# MEFI.net
KiCad netlist of a schematic drawn in EAGLE
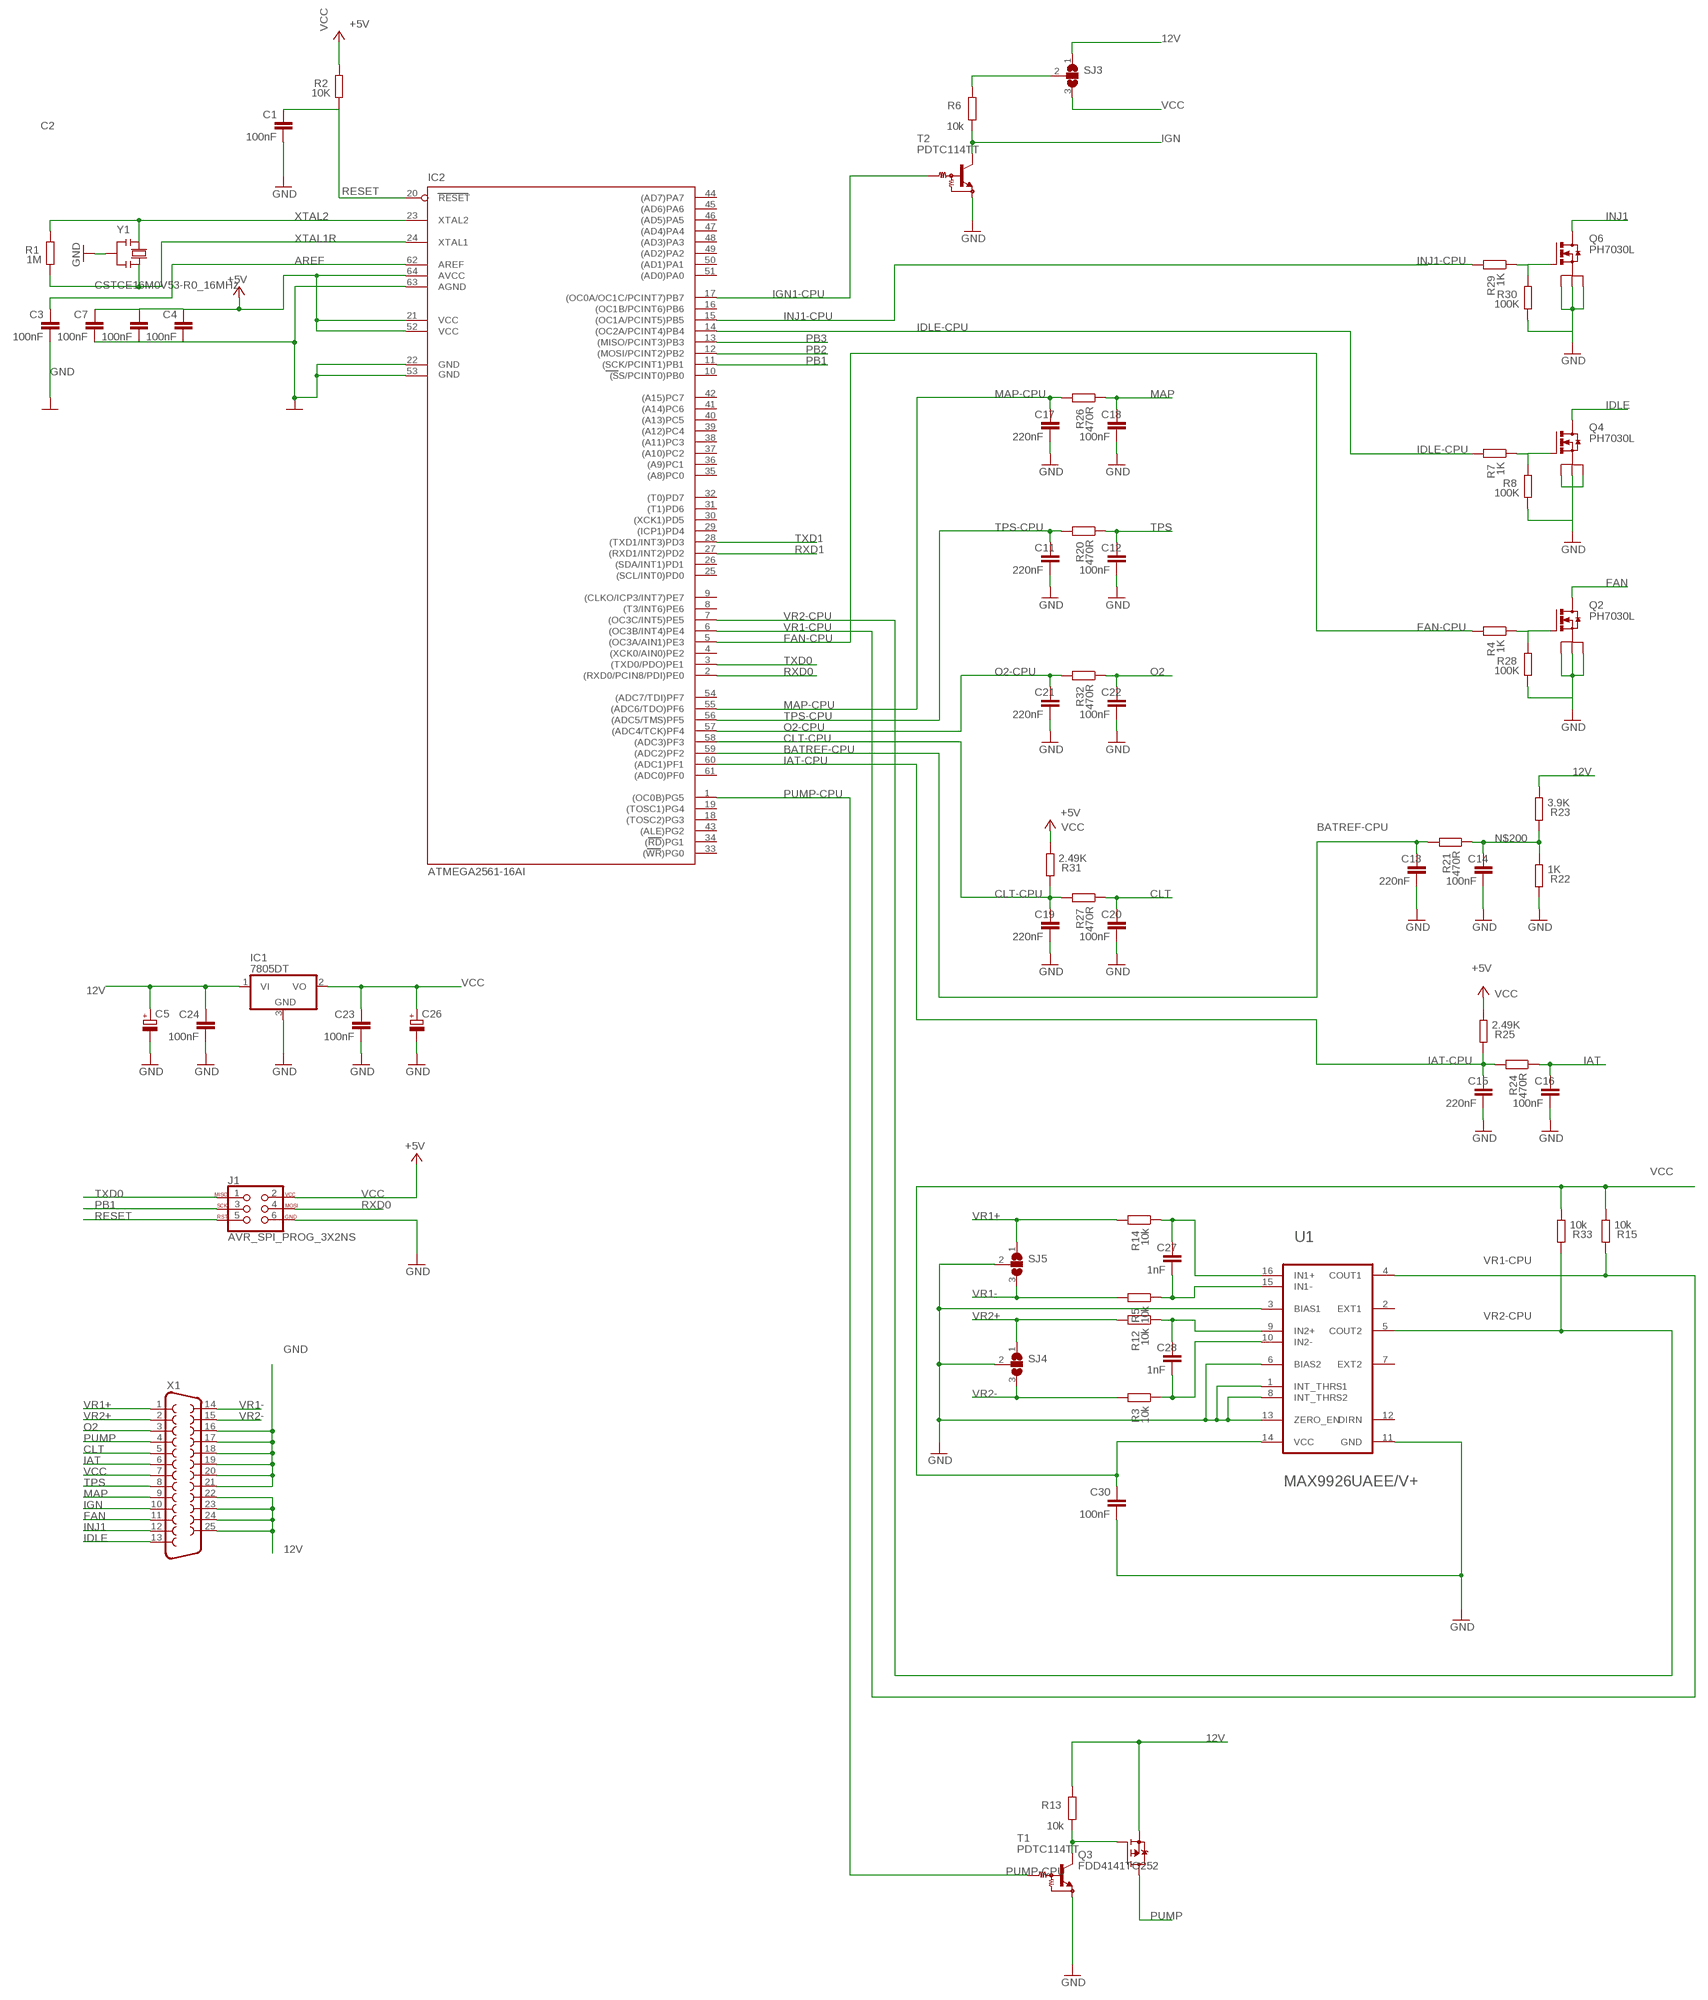
[diagram p0: schematic, sheet 1]

(export (version "E")
  (design (tool "Eeschema 10.0.6"))
  (components
    (comp (ref "C1")
      (value "100nF")
      (footprint "eagle-import:C0805")
      (libsource (lib "eagle-import") (part "C-EUC0805"))
    )
    (comp (ref "C2")
      (value "100nF")
      (footprint "eagle-import:C0805")
      (libsource (lib "eagle-import") (part "C-EUC0805"))
    )
    (comp (ref "C3")
      (value "100nF")
      (footprint "eagle-import:C0805")
      (libsource (lib "eagle-import") (part "C-EUC0805"))
    )
    (comp (ref "C4")
      (value "100nF")
      (footprint "eagle-import:C0805")
      (libsource (lib "eagle-import") (part "C-EUC0805"))
    )
    (comp (ref "C5")
      (value "CPOL-EUTT2D7L")
      (footprint "eagle-import:TT2D7L")
      (libsource (lib "eagle-import") (part "CPOL-EUTT2D7L"))
    )
    (comp (ref "C7")
      (value "100nF")
      (footprint "eagle-import:C0805")
      (libsource (lib "eagle-import") (part "C-EUC0805"))
    )
    (comp (ref "C11")
      (value "220nF")
      (footprint "eagle-import:C0805")
      (libsource (lib "eagle-import") (part "C-EUC0805"))
    )
    (comp (ref "C12")
      (value "100nF")
      (footprint "eagle-import:C0805")
      (libsource (lib "eagle-import") (part "C-EUC0805"))
    )
    (comp (ref "C13")
      (value "220nF")
      (footprint "eagle-import:C0805")
      (libsource (lib "eagle-import") (part "C-EUC0805"))
    )
    (comp (ref "C14")
      (value "100nF")
      (footprint "eagle-import:C0805")
      (libsource (lib "eagle-import") (part "C-EUC0805"))
    )
    (comp (ref "C15")
      (value "220nF")
      (footprint "eagle-import:C0805")
      (libsource (lib "eagle-import") (part "C-EUC0805"))
    )
    (comp (ref "C16")
      (value "100nF")
      (footprint "eagle-import:C0805")
      (libsource (lib "eagle-import") (part "C-EUC0805"))
    )
    (comp (ref "C17")
      (value "220nF")
      (footprint "eagle-import:C0805")
      (fields (field (name "SPICEPREFIX") "C"))
      (libsource (lib "eagle-import") (part "C-EUC0805"))
    )
    (comp (ref "C18")
      (value "100nF")
      (footprint "eagle-import:C0805")
      (libsource (lib "eagle-import") (part "C-EUC0805"))
    )
    (comp (ref "C19")
      (value "220nF")
      (footprint "eagle-import:C0805")
      (libsource (lib "eagle-import") (part "C-EUC0805"))
    )
    (comp (ref "C20")
      (value "100nF")
      (footprint "eagle-import:C0805")
      (libsource (lib "eagle-import") (part "C-EUC0805"))
    )
    (comp (ref "C21")
      (value "220nF")
      (footprint "eagle-import:C0805")
      (libsource (lib "eagle-import") (part "C-EUC0805"))
    )
    (comp (ref "C22")
      (value "100nF")
      (footprint "eagle-import:C0805")
      (libsource (lib "eagle-import") (part "C-EUC0805"))
    )
    (comp (ref "C23")
      (value "100nF")
      (footprint "eagle-import:C0805")
      (libsource (lib "eagle-import") (part "C-EUC0805"))
    )
    (comp (ref "C24")
      (value "100nF")
      (footprint "eagle-import:C0805")
      (libsource (lib "eagle-import") (part "C-EUC0805"))
    )
    (comp (ref "C26")
      (value "CPOL-EUTT2D7L")
      (footprint "eagle-import:TT2D7L")
      (libsource (lib "eagle-import") (part "CPOL-EUTT2D7L"))
    )
    (comp (ref "C27")
      (value "1nF")
      (footprint "eagle-import:C0805")
      (libsource (lib "eagle-import") (part "C-EUC0805"))
    )
    (comp (ref "C28")
      (value "1nF")
      (footprint "eagle-import:C0805")
      (libsource (lib "eagle-import") (part "C-EUC0805"))
    )
    (comp (ref "C30")
      (value "100nF")
      (footprint "eagle-import:C0805")
      (libsource (lib "eagle-import") (part "C-EUC0805"))
    )
    (comp (ref "IC1")
      (value "7805DT")
      (footprint "eagle-import:TO252")
      (libsource (lib "eagle-import") (part "78DT05"))
    )
    (comp (ref "IC2")
      (value "ATMEGA2561-16AI")
      (footprint "eagle-import:TQFP64")
      (libsource (lib "eagle-import") (part "ATMEGA2561AI-16"))
    )
    (comp (ref "J1")
      (value "AVR_SPI_PROG_3X2NS")
      (footprint "eagle-import:2X3-NS")
      (fields (field (name "SPICEPREFIX") "X"))
      (libsource (lib "eagle-import") (part "AVR_SPI_PROG_3X2NS"))
    )
    (comp (ref "Q2")
      (value "PH7030L")
      (footprint "eagle-import:SOT669")
      (libsource (lib "eagle-import") (part "PH7030L"))
    )
    (comp (ref "Q3")
      (value "FDD4141TO252")
      (footprint "eagle-import:TO252")
      (libsource (lib "eagle-import") (part "FDD4141TO252"))
    )
    (comp (ref "Q4")
      (value "PH7030L")
      (footprint "eagle-import:SOT669")
      (libsource (lib "eagle-import") (part "PH7030L"))
    )
    (comp (ref "Q6")
      (value "PH7030L")
      (footprint "eagle-import:SOT669")
      (libsource (lib "eagle-import") (part "PH7030L"))
    )
    (comp (ref "R1")
      (value "1M")
      (footprint "eagle-import:R0805")
      (libsource (lib "eagle-import") (part "R-EU_R0805"))
    )
    (comp (ref "R2")
      (value "10K")
      (footprint "eagle-import:R0805")
      (libsource (lib "eagle-import") (part "R-EU_R0805"))
    )
    (comp (ref "R3")
      (value "10k")
      (footprint "eagle-import:R0805")
      (libsource (lib "eagle-import") (part "R-EU_R0805"))
    )
    (comp (ref "R4")
      (value "1K")
      (footprint "eagle-import:R0805")
      (libsource (lib "eagle-import") (part "R-EU_R0805"))
    )
    (comp (ref "R5")
      (value "10k")
      (footprint "eagle-import:R0805")
      (libsource (lib "eagle-import") (part "R-EU_R0805"))
    )
    (comp (ref "R6")
      (value "10k")
      (footprint "eagle-import:R0805")
      (libsource (lib "eagle-import") (part "R-EU_R0805"))
    )
    (comp (ref "R7")
      (value "1K")
      (footprint "eagle-import:R0805")
      (libsource (lib "eagle-import") (part "R-EU_R0805"))
    )
    (comp (ref "R8")
      (value "100K")
      (footprint "eagle-import:R0805")
      (libsource (lib "eagle-import") (part "R-EU_R0805"))
    )
    (comp (ref "R12")
      (value "10k")
      (footprint "eagle-import:R0805")
      (libsource (lib "eagle-import") (part "R-EU_R0805"))
    )
    (comp (ref "R13")
      (value "10k")
      (footprint "eagle-import:R0805")
      (libsource (lib "eagle-import") (part "R-EU_R0805"))
    )
    (comp (ref "R14")
      (value "10k")
      (footprint "eagle-import:R0805")
      (libsource (lib "eagle-import") (part "R-EU_R0805"))
    )
    (comp (ref "R15")
      (value "10k")
      (footprint "eagle-import:R0805")
      (libsource (lib "eagle-import") (part "R-EU_R0805"))
    )
    (comp (ref "R20")
      (value "470R")
      (footprint "eagle-import:R0805")
      (libsource (lib "eagle-import") (part "R-EU_R0805"))
    )
    (comp (ref "R21")
      (value "470R")
      (footprint "eagle-import:R0805")
      (libsource (lib "eagle-import") (part "R-EU_R0805"))
    )
    (comp (ref "R22")
      (value "1K")
      (footprint "eagle-import:R0805")
      (libsource (lib "eagle-import") (part "R-EU_R0805"))
    )
    (comp (ref "R23")
      (value "3.9K")
      (footprint "eagle-import:R0805")
      (libsource (lib "eagle-import") (part "R-EU_R0805"))
    )
    (comp (ref "R24")
      (value "470R")
      (footprint "eagle-import:R0805")
      (libsource (lib "eagle-import") (part "R-EU_R0805"))
    )
    (comp (ref "R25")
      (value "2.49K")
      (footprint "eagle-import:R0805")
      (libsource (lib "eagle-import") (part "R-EU_R0805"))
    )
    (comp (ref "R26")
      (value "470R")
      (footprint "eagle-import:R0805")
      (libsource (lib "eagle-import") (part "R-EU_R0805"))
    )
    (comp (ref "R27")
      (value "470R")
      (footprint "eagle-import:R0805")
      (libsource (lib "eagle-import") (part "R-EU_R0805"))
    )
    (comp (ref "R28")
      (value "100K")
      (footprint "eagle-import:R0805")
      (libsource (lib "eagle-import") (part "R-EU_R0805"))
    )
    (comp (ref "R29")
      (value "1K")
      (footprint "eagle-import:R0805")
      (libsource (lib "eagle-import") (part "R-EU_R0805"))
    )
    (comp (ref "R30")
      (value "100K")
      (footprint "eagle-import:R0805")
      (libsource (lib "eagle-import") (part "R-EU_R0805"))
    )
    (comp (ref "R31")
      (value "2.49K")
      (footprint "eagle-import:R0805")
      (libsource (lib "eagle-import") (part "R-EU_R0805"))
    )
    (comp (ref "R32")
      (value "470R")
      (footprint "eagle-import:R0805")
      (libsource (lib "eagle-import") (part "R-EU_R0805"))
    )
    (comp (ref "R33")
      (value "10k")
      (footprint "eagle-import:R0805")
      (libsource (lib "eagle-import") (part "R-EU_R0805"))
    )
    (comp (ref "SJ3")
      (value "SJ2W")
      (footprint "eagle-import:SJ_2")
      (libsource (lib "eagle-import") (part "SJ2W"))
    )
    (comp (ref "SJ4")
      (value "SJ2W")
      (footprint "eagle-import:SJ_2")
      (libsource (lib "eagle-import") (part "SJ2W"))
    )
    (comp (ref "SJ5")
      (value "SJ2W")
      (footprint "eagle-import:SJ_2")
      (libsource (lib "eagle-import") (part "SJ2W"))
    )
    (comp (ref "T1")
      (value "PDTC114TT")
      (footprint "eagle-import:SC59-BEC")
      (libsource (lib "eagle-import") (part "-NPN_DRIVER-SC59-BECMUN2214T1"))
    )
    (comp (ref "T2")
      (value "PDTC114TT")
      (footprint "eagle-import:SC59-BEC")
      (libsource (lib "eagle-import") (part "-NPN_DRIVER-SC59-BECMUN2214T1"))
    )
    (comp (ref "U1")
      (value "MAXIM_MAX9926UAEE-V+MAXIM_MAX9926UAEE-V+_0_0")
      (footprint "eagle-import:MAXIM_MAX9926UAEE-V+_0")
      (fields (field (name "MF") "Maxim") (field (name "MPN") "MAX9926UAEE/V+"))
      (libsource (lib "eagle-import") (part "MAXIM_MAX9926UAEE-V+MAXIM_MAX9926UAEE-V+_0_0"))
    )
    (comp (ref "X1")
      (value "F25D")
      (footprint "eagle-import:F25D")
      (libsource (lib "eagle-import") (part "F25D"))
    )
    (comp (ref "Y1")
      (value "CSTCE16M0V53-R0_16MHz")
      (footprint "eagle-import:RESONATOR")
      (libsource (lib "eagle-import") (part "RESONATORMU"))
    )
  )
  (nets
    (net (code "1") (name "+5V") (class "Default")
      (node (ref "C2") (pin "1") (pinfunction "1_1") (pintype "passive"))
      (node (ref "C23") (pin "1") (pinfunction "1_1") (pintype "passive"))
      (node (ref "C26") (pin "+") (pinfunction "+_+") (pintype "passive"))
      (node (ref "C30") (pin "1") (pinfunction "1_1") (pintype "passive"))
      (node (ref "C4") (pin "1") (pinfunction "1_1") (pintype "passive"))
      (node (ref "C7") (pin "1") (pinfunction "1_1") (pintype "passive"))
      (node (ref "IC1") (pin "2") (pinfunction "VO_2") (pintype "passive"))
      (node (ref "IC2") (pin "21") (pinfunction "VCC_21") (pintype "power_in"))
      (node (ref "IC2") (pin "52") (pinfunction "VCC1_52") (pintype "power_in"))
      (node (ref "IC2") (pin "64") (pinfunction "AVCC_64") (pintype "power_in"))
      (node (ref "J1") (pin "2") (pinfunction "2_2") (pintype "passive"))
      (node (ref "R15") (pin "1") (pinfunction "1_1") (pintype "passive"))
      (node (ref "R2") (pin "2") (pinfunction "2_2") (pintype "passive"))
      (node (ref "R25") (pin "1") (pinfunction "1_1") (pintype "passive"))
      (node (ref "R31") (pin "1") (pinfunction "1_1") (pintype "passive"))
      (node (ref "R33") (pin "1") (pinfunction "1_1") (pintype "passive"))
      (node (ref "SJ3") (pin "3") (pinfunction "3_3") (pintype "passive"))
      (node (ref "U1") (pin "14") (pinfunction "VCC_14") (pintype "power_in"))
      (node (ref "X1") (pin "7") (pinfunction "7_7") (pintype "passive"))
    )
    (net (code "2") (name "/12V") (class "Default")
      (node (ref "C24") (pin "1") (pinfunction "1_1") (pintype "passive"))
      (node (ref "C5") (pin "+") (pinfunction "+_+") (pintype "passive"))
      (node (ref "IC1") (pin "1") (pinfunction "VI_1") (pintype "input"))
      (node (ref "Q3") (pin "2") (pinfunction "S_2") (pintype "passive"))
      (node (ref "R13") (pin "2") (pinfunction "2_2") (pintype "passive"))
      (node (ref "R23") (pin "1") (pinfunction "1_1") (pintype "passive"))
      (node (ref "SJ3") (pin "1") (pinfunction "1_1") (pintype "passive"))
      (node (ref "X1") (pin "22") (pinfunction "22_22") (pintype "passive"))
      (node (ref "X1") (pin "23") (pinfunction "23_23") (pintype "passive"))
      (node (ref "X1") (pin "24") (pinfunction "24_24") (pintype "passive"))
      (node (ref "X1") (pin "25") (pinfunction "25_25") (pintype "passive"))
    )
    (net (code "3") (name "/AREF") (class "Default")
      (node (ref "C3") (pin "1") (pinfunction "1_1") (pintype "passive"))
      (node (ref "IC2") (pin "62") (pinfunction "AREF_62") (pintype "bidirectional"))
    )
    (net (code "4") (name "/BATREF-CPU") (class "Default")
      (node (ref "C13") (pin "1") (pinfunction "1_1") (pintype "passive"))
      (node (ref "IC2") (pin "59") (pinfunction "(ADC2)PF2_59") (pintype "bidirectional"))
      (node (ref "R21") (pin "2") (pinfunction "2_2") (pintype "passive"))
    )
    (net (code "5") (name "/CLT") (class "Default")
      (node (ref "C20") (pin "1") (pinfunction "1_1") (pintype "passive"))
      (node (ref "R27") (pin "1") (pinfunction "1_1") (pintype "passive"))
      (node (ref "X1") (pin "5") (pinfunction "5_5") (pintype "passive"))
    )
    (net (code "6") (name "/CLT-CPU") (class "Default")
      (node (ref "C19") (pin "1") (pinfunction "1_1") (pintype "passive"))
      (node (ref "IC2") (pin "58") (pinfunction "(ADC3)PF3_58") (pintype "bidirectional"))
      (node (ref "R27") (pin "2") (pinfunction "2_2") (pintype "passive"))
      (node (ref "R31") (pin "2") (pinfunction "2_2") (pintype "passive"))
    )
    (net (code "7") (name "/FAN") (class "Default")
      (node (ref "Q2") (pin "MB") (pinfunction "D_MB") (pintype "passive"))
      (node (ref "X1") (pin "11") (pinfunction "11_11") (pintype "passive"))
    )
    (net (code "8") (name "/FAN-CPU") (class "Default")
      (node (ref "IC2") (pin "5") (pinfunction "(OC3A/AIN1)PE3_5") (pintype "bidirectional"))
      (node (ref "R4") (pin "2") (pinfunction "2_2") (pintype "passive"))
    )
    (net (code "9") (name "/IAT") (class "Default")
      (node (ref "C16") (pin "1") (pinfunction "1_1") (pintype "passive"))
      (node (ref "R24") (pin "1") (pinfunction "1_1") (pintype "passive"))
      (node (ref "X1") (pin "6") (pinfunction "6_6") (pintype "passive"))
    )
    (net (code "10") (name "/IAT-CPU") (class "Default")
      (node (ref "C15") (pin "1") (pinfunction "1_1") (pintype "passive"))
      (node (ref "IC2") (pin "60") (pinfunction "(ADC1)PF1_60") (pintype "bidirectional"))
      (node (ref "R24") (pin "2") (pinfunction "2_2") (pintype "passive"))
      (node (ref "R25") (pin "2") (pinfunction "2_2") (pintype "passive"))
    )
    (net (code "11") (name "/IDLE") (class "Default")
      (node (ref "Q4") (pin "MB") (pinfunction "D_MB") (pintype "passive"))
      (node (ref "X1") (pin "13") (pinfunction "13_13") (pintype "passive"))
    )
    (net (code "12") (name "/IDLE-CPU") (class "Default")
      (node (ref "IC2") (pin "14") (pinfunction "(OC2A/PCINT4)PB4_14") (pintype "bidirectional"))
      (node (ref "R7") (pin "2") (pinfunction "2_2") (pintype "passive"))
    )
    (net (code "13") (name "/IGN") (class "Default")
      (node (ref "R6") (pin "1") (pinfunction "1_1") (pintype "passive"))
      (node (ref "T2") (pin "C") (pinfunction "C_C") (pintype "passive"))
      (node (ref "X1") (pin "10") (pinfunction "10_10") (pintype "passive"))
    )
    (net (code "14") (name "/IGN1-CPU") (class "Default")
      (node (ref "IC2") (pin "17") (pinfunction "(OC0A/OC1C/PCINT7)PB7_17") (pintype "bidirectional"))
      (node (ref "T2") (pin "B") (pinfunction "B_B") (pintype "passive"))
    )
    (net (code "15") (name "/INJ1") (class "Default")
      (node (ref "Q6") (pin "MB") (pinfunction "D_MB") (pintype "passive"))
      (node (ref "X1") (pin "12") (pinfunction "12_12") (pintype "passive"))
    )
    (net (code "16") (name "/INJ1-CPU") (class "Default")
      (node (ref "IC2") (pin "15") (pinfunction "(OC1A/PCINT5)PB5_15") (pintype "bidirectional"))
      (node (ref "R29") (pin "2") (pinfunction "2_2") (pintype "passive"))
    )
    (net (code "17") (name "/MAP") (class "Default")
      (node (ref "C18") (pin "1") (pinfunction "1_1") (pintype "passive"))
      (node (ref "R26") (pin "1") (pinfunction "1_1") (pintype "passive"))
      (node (ref "X1") (pin "9") (pinfunction "9_9") (pintype "passive"))
    )
    (net (code "18") (name "/MAP-CPU") (class "Default")
      (node (ref "C17") (pin "1") (pinfunction "1_1") (pintype "passive"))
      (node (ref "IC2") (pin "55") (pinfunction "(ADC6/TDO)PF6_55") (pintype "bidirectional"))
      (node (ref "R26") (pin "2") (pinfunction "2_2") (pintype "passive"))
    )
    (net (code "19") (name "/N$200") (class "Default")
      (node (ref "C14") (pin "1") (pinfunction "1_1") (pintype "passive"))
      (node (ref "R21") (pin "1") (pinfunction "1_1") (pintype "passive"))
      (node (ref "R22") (pin "1") (pinfunction "1_1") (pintype "passive"))
      (node (ref "R23") (pin "2") (pinfunction "2_2") (pintype "passive"))
    )
    (net (code "20") (name "/O2") (class "Default")
      (node (ref "C22") (pin "1") (pinfunction "1_1") (pintype "passive"))
      (node (ref "R32") (pin "1") (pinfunction "1_1") (pintype "passive"))
      (node (ref "X1") (pin "3") (pinfunction "3_3") (pintype "passive"))
    )
    (net (code "21") (name "/O2-CPU") (class "Default")
      (node (ref "C21") (pin "1") (pinfunction "1_1") (pintype "passive"))
      (node (ref "IC2") (pin "57") (pinfunction "(ADC4/TCK)PF4_57") (pintype "bidirectional"))
      (node (ref "R32") (pin "2") (pinfunction "2_2") (pintype "passive"))
    )
    (net (code "22") (name "/PB1") (class "Default")
      (node (ref "IC2") (pin "11") (pinfunction "(SCK/PCINT1)PB1_11") (pintype "bidirectional"))
      (node (ref "J1") (pin "3") (pinfunction "3_3") (pintype "passive"))
    )
    (net (code "23") (name "/PB2") (class "Default")
      (node (ref "IC2") (pin "12") (pinfunction "(MOSI/PCINT2)PB2_12") (pintype "bidirectional"))
    )
    (net (code "24") (name "/PB3") (class "Default")
      (node (ref "IC2") (pin "13") (pinfunction "(MISO/PCINT3)PB3_13") (pintype "bidirectional"))
    )
    (net (code "25") (name "/PUMP") (class "Default")
      (node (ref "Q3") (pin "3") (pinfunction "D_3") (pintype "passive"))
      (node (ref "X1") (pin "4") (pinfunction "4_4") (pintype "passive"))
    )
    (net (code "26") (name "/PUMP-CPU") (class "Default")
      (node (ref "IC2") (pin "1") (pinfunction "(OC0B)PG5_1") (pintype "bidirectional"))
      (node (ref "T1") (pin "B") (pinfunction "B_B") (pintype "passive"))
    )
    (net (code "27") (name "/RESET") (class "Default")
      (node (ref "C1") (pin "1") (pinfunction "1_1") (pintype "passive"))
      (node (ref "IC2") (pin "20") (pinfunction "RESET_20") (pintype "input"))
      (node (ref "J1") (pin "5") (pinfunction "5_5") (pintype "passive"))
      (node (ref "R2") (pin "1") (pinfunction "1_1") (pintype "passive"))
    )
    (net (code "28") (name "/RXD0") (class "Default")
      (node (ref "IC2") (pin "2") (pinfunction "(RXD0/PCIN8/PDI)PE0_2") (pintype "bidirectional"))
      (node (ref "J1") (pin "4") (pinfunction "4_4") (pintype "passive"))
    )
    (net (code "29") (name "/RXD1") (class "Default")
      (node (ref "IC2") (pin "27") (pinfunction "(RXD1/INT2)PD2_27") (pintype "bidirectional"))
    )
    (net (code "30") (name "/TPS") (class "Default")
      (node (ref "C12") (pin "1") (pinfunction "1_1") (pintype "passive"))
      (node (ref "R20") (pin "1") (pinfunction "1_1") (pintype "passive"))
      (node (ref "X1") (pin "8") (pinfunction "8_8") (pintype "passive"))
    )
    (net (code "31") (name "/TPS-CPU") (class "Default")
      (node (ref "C11") (pin "1") (pinfunction "1_1") (pintype "passive"))
      (node (ref "IC2") (pin "56") (pinfunction "(ADC5/TMS)PF5_56") (pintype "bidirectional"))
      (node (ref "R20") (pin "2") (pinfunction "2_2") (pintype "passive"))
    )
    (net (code "32") (name "/TXD0") (class "Default")
      (node (ref "IC2") (pin "3") (pinfunction "(TXD0/PDO)PE1_3") (pintype "bidirectional"))
      (node (ref "J1") (pin "1") (pinfunction "1_1") (pintype "passive"))
    )
    (net (code "33") (name "/TXD1") (class "Default")
      (node (ref "IC2") (pin "28") (pinfunction "(TXD1/INT3)PD3_28") (pintype "bidirectional"))
    )
    (net (code "34") (name "/VR1+") (class "Default")
      (node (ref "R14") (pin "2") (pinfunction "2_2") (pintype "passive"))
      (node (ref "SJ5") (pin "1") (pinfunction "1_1") (pintype "passive"))
      (node (ref "X1") (pin "1") (pinfunction "1_1") (pintype "passive"))
    )
    (net (code "35") (name "/VR1-") (class "Default")
      (node (ref "R5") (pin "2") (pinfunction "2_2") (pintype "passive"))
      (node (ref "SJ5") (pin "3") (pinfunction "3_3") (pintype "passive"))
      (node (ref "X1") (pin "14") (pinfunction "14_14") (pintype "passive"))
    )
    (net (code "36") (name "/VR1-CPU") (class "Default")
      (node (ref "IC2") (pin "6") (pinfunction "(OC3B/INT4)PE4_6") (pintype "bidirectional"))
      (node (ref "R15") (pin "2") (pinfunction "2_2") (pintype "passive"))
      (node (ref "U1") (pin "4") (pinfunction "COUT1_4") (pintype "open_collector"))
    )
    (net (code "37") (name "/VR2+") (class "Default")
      (node (ref "R12") (pin "2") (pinfunction "2_2") (pintype "passive"))
      (node (ref "SJ4") (pin "1") (pinfunction "1_1") (pintype "passive"))
      (node (ref "X1") (pin "2") (pinfunction "2_2") (pintype "passive"))
    )
    (net (code "38") (name "/VR2-") (class "Default")
      (node (ref "R3") (pin "2") (pinfunction "2_2") (pintype "passive"))
      (node (ref "SJ4") (pin "3") (pinfunction "3_3") (pintype "passive"))
      (node (ref "X1") (pin "15") (pinfunction "15_15") (pintype "passive"))
    )
    (net (code "39") (name "/VR2-CPU") (class "Default")
      (node (ref "IC2") (pin "7") (pinfunction "(OC3C/INT5)PE5_7") (pintype "bidirectional"))
      (node (ref "R33") (pin "2") (pinfunction "2_2") (pintype "passive"))
      (node (ref "U1") (pin "5") (pinfunction "COUT2_5") (pintype "open_collector"))
    )
    (net (code "40") (name "/XTAL1R") (class "Default")
      (node (ref "IC2") (pin "24") (pinfunction "XTAL1_24") (pintype "input"))
      (node (ref "R1") (pin "1") (pinfunction "1_1") (pintype "passive"))
      (node (ref "Y1") (pin "3") (pinfunction "3_3") (pintype "passive"))
    )
    (net (code "41") (name "/XTAL2") (class "Default")
      (node (ref "IC2") (pin "23") (pinfunction "XTAL2_23") (pintype "output"))
      (node (ref "R1") (pin "2") (pinfunction "2_2") (pintype "passive"))
      (node (ref "Y1") (pin "1") (pinfunction "1_1") (pintype "passive"))
    )
    (net (code "42") (name "GND") (class "Default")
      (node (ref "C1") (pin "2") (pinfunction "2_2") (pintype "passive"))
      (node (ref "C11") (pin "2") (pinfunction "2_2") (pintype "passive"))
      (node (ref "C12") (pin "2") (pinfunction "2_2") (pintype "passive"))
      (node (ref "C13") (pin "2") (pinfunction "2_2") (pintype "passive"))
      (node (ref "C14") (pin "2") (pinfunction "2_2") (pintype "passive"))
      (node (ref "C15") (pin "2") (pinfunction "2_2") (pintype "passive"))
      (node (ref "C16") (pin "2") (pinfunction "2_2") (pintype "passive"))
      (node (ref "C17") (pin "2") (pinfunction "2_2") (pintype "passive"))
      (node (ref "C18") (pin "2") (pinfunction "2_2") (pintype "passive"))
      (node (ref "C19") (pin "2") (pinfunction "2_2") (pintype "passive"))
      (node (ref "C2") (pin "2") (pinfunction "2_2") (pintype "passive"))
      (node (ref "C20") (pin "2") (pinfunction "2_2") (pintype "passive"))
      (node (ref "C21") (pin "2") (pinfunction "2_2") (pintype "passive"))
      (node (ref "C22") (pin "2") (pinfunction "2_2") (pintype "passive"))
      (node (ref "C23") (pin "2") (pinfunction "2_2") (pintype "passive"))
      (node (ref "C24") (pin "2") (pinfunction "2_2") (pintype "passive"))
      (node (ref "C26") (pin "-") (pinfunction "-_-") (pintype "passive"))
      (node (ref "C3") (pin "2") (pinfunction "2_2") (pintype "passive"))
      (node (ref "C30") (pin "2") (pinfunction "2_2") (pintype "passive"))
      (node (ref "C4") (pin "2") (pinfunction "2_2") (pintype "passive"))
      (node (ref "C5") (pin "-") (pinfunction "-_-") (pintype "passive"))
      (node (ref "C7") (pin "2") (pinfunction "2_2") (pintype "passive"))
      (node (ref "IC1") (pin "3") (pinfunction "GND_3") (pintype "passive"))
      (node (ref "IC2") (pin "22") (pinfunction "GND_22") (pintype "power_in"))
      (node (ref "IC2") (pin "53") (pinfunction "GND1_53") (pintype "power_in"))
      (node (ref "IC2") (pin "63") (pinfunction "AGND_63") (pintype "power_in"))
      (node (ref "J1") (pin "6") (pinfunction "6_6") (pintype "passive"))
      (node (ref "Q2") (pin "1") (pinfunction "S_1") (pintype "passive"))
      (node (ref "Q2") (pin "2") (pinfunction "S_2") (pintype "passive"))
      (node (ref "Q2") (pin "3") (pinfunction "S_3") (pintype "passive"))
      (node (ref "Q4") (pin "1") (pinfunction "S_1") (pintype "passive"))
      (node (ref "Q4") (pin "2") (pinfunction "S_2") (pintype "passive"))
      (node (ref "Q4") (pin "3") (pinfunction "S_3") (pintype "passive"))
      (node (ref "Q6") (pin "1") (pinfunction "S_1") (pintype "passive"))
      (node (ref "Q6") (pin "2") (pinfunction "S_2") (pintype "passive"))
      (node (ref "Q6") (pin "3") (pinfunction "S_3") (pintype "passive"))
      (node (ref "R22") (pin "2") (pinfunction "2_2") (pintype "passive"))
      (node (ref "R28") (pin "1") (pinfunction "1_1") (pintype "passive"))
      (node (ref "R30") (pin "1") (pinfunction "1_1") (pintype "passive"))
      (node (ref "R8") (pin "1") (pinfunction "1_1") (pintype "passive"))
      (node (ref "SJ4") (pin "2") (pinfunction "2_2") (pintype "passive"))
      (node (ref "SJ5") (pin "2") (pinfunction "2_2") (pintype "passive"))
      (node (ref "T1") (pin "E") (pinfunction "E_E") (pintype "passive"))
      (node (ref "T2") (pin "E") (pinfunction "E_E") (pintype "passive"))
      (node (ref "U1") (pin "1") (pinfunction "INT_THRS1_1") (pintype "input"))
      (node (ref "U1") (pin "11") (pinfunction "GND_11") (pintype "power_in"))
      (node (ref "U1") (pin "13") (pinfunction "ZERO_EN_13") (pintype "input"))
      (node (ref "U1") (pin "3") (pinfunction "BIAS1_3") (pintype "input"))
      (node (ref "U1") (pin "6") (pinfunction "BIAS2_6") (pintype "input"))
      (node (ref "U1") (pin "8") (pinfunction "INT_THRS2_8") (pintype "input"))
      (node (ref "X1") (pin "16") (pinfunction "16_16") (pintype "passive"))
      (node (ref "X1") (pin "17") (pinfunction "17_17") (pintype "passive"))
      (node (ref "X1") (pin "18") (pinfunction "18_18") (pintype "passive"))
      (node (ref "X1") (pin "19") (pinfunction "19_19") (pintype "passive"))
      (node (ref "X1") (pin "20") (pinfunction "20_20") (pintype "passive"))
      (node (ref "X1") (pin "21") (pinfunction "21_21") (pintype "passive"))
      (node (ref "Y1") (pin "2") (pinfunction "2_2") (pintype "passive"))
    )
    (net (code "43") (name "Net-(Q2-G)") (class "Default")
      (node (ref "Q2") (pin "4") (pinfunction "G_4") (pintype "passive"))
      (node (ref "R28") (pin "2") (pinfunction "2_2") (pintype "passive"))
      (node (ref "R4") (pin "1") (pinfunction "1_1") (pintype "passive"))
    )
    (net (code "44") (name "Net-(Q3-G)") (class "Default")
      (node (ref "Q3") (pin "1") (pinfunction "G_1") (pintype "passive"))
      (node (ref "R13") (pin "1") (pinfunction "1_1") (pintype "passive"))
      (node (ref "T1") (pin "C") (pinfunction "C_C") (pintype "passive"))
    )
    (net (code "45") (name "Net-(Q4-G)") (class "Default")
      (node (ref "Q4") (pin "4") (pinfunction "G_4") (pintype "passive"))
      (node (ref "R7") (pin "1") (pinfunction "1_1") (pintype "passive"))
      (node (ref "R8") (pin "2") (pinfunction "2_2") (pintype "passive"))
    )
    (net (code "46") (name "Net-(Q6-G)") (class "Default")
      (node (ref "Q6") (pin "4") (pinfunction "G_4") (pintype "passive"))
      (node (ref "R29") (pin "1") (pinfunction "1_1") (pintype "passive"))
      (node (ref "R30") (pin "2") (pinfunction "2_2") (pintype "passive"))
    )
    (net (code "47") (name "Net-(R6-Pad2)") (class "Default")
      (node (ref "R6") (pin "2") (pinfunction "2_2") (pintype "passive"))
      (node (ref "SJ3") (pin "2") (pinfunction "2_2") (pintype "passive"))
    )
    (net (code "48") (name "Net-(U1-IN1+)") (class "Default")
      (node (ref "C27") (pin "1") (pinfunction "1_1") (pintype "passive"))
      (node (ref "R14") (pin "1") (pinfunction "1_1") (pintype "passive"))
      (node (ref "U1") (pin "16") (pinfunction "IN1+_16") (pintype "input"))
    )
    (net (code "49") (name "Net-(U1-IN1-)") (class "Default")
      (node (ref "C27") (pin "2") (pinfunction "2_2") (pintype "passive"))
      (node (ref "R5") (pin "1") (pinfunction "1_1") (pintype "passive"))
      (node (ref "U1") (pin "15") (pinfunction "IN1-_15") (pintype "input"))
    )
    (net (code "50") (name "Net-(U1-IN2+)") (class "Default")
      (node (ref "C28") (pin "1") (pinfunction "1_1") (pintype "passive"))
      (node (ref "R12") (pin "1") (pinfunction "1_1") (pintype "passive"))
      (node (ref "U1") (pin "9") (pinfunction "IN2+_9") (pintype "input"))
    )
    (net (code "51") (name "Net-(U1-IN2-)") (class "Default")
      (node (ref "C28") (pin "2") (pinfunction "2_2") (pintype "passive"))
      (node (ref "R3") (pin "1") (pinfunction "1_1") (pintype "passive"))
      (node (ref "U1") (pin "10") (pinfunction "IN2-_10") (pintype "input"))
    )
    (net (code "52") (name "unconnected-(IC2-(A8)PC0-Pad35)") (class "Default")
      (node (ref "IC2") (pin "35") (pinfunction "(A8)PC0_35") (pintype "bidirectional"))
    )
    (net (code "53") (name "unconnected-(IC2-(A9)PC1-Pad36)") (class "Default")
      (node (ref "IC2") (pin "36") (pinfunction "(A9)PC1_36") (pintype "bidirectional"))
    )
    (net (code "54") (name "unconnected-(IC2-(A10)PC2-Pad37)") (class "Default")
      (node (ref "IC2") (pin "37") (pinfunction "(A10)PC2_37") (pintype "bidirectional"))
    )
    (net (code "55") (name "unconnected-(IC2-(A11)PC3-Pad38)") (class "Default")
      (node (ref "IC2") (pin "38") (pinfunction "(A11)PC3_38") (pintype "bidirectional"))
    )
    (net (code "56") (name "unconnected-(IC2-(A12)PC4-Pad39)") (class "Default")
      (node (ref "IC2") (pin "39") (pinfunction "(A12)PC4_39") (pintype "bidirectional"))
    )
    (net (code "57") (name "unconnected-(IC2-(A13)PC5-Pad40)") (class "Default")
      (node (ref "IC2") (pin "40") (pinfunction "(A13)PC5_40") (pintype "bidirectional"))
    )
    (net (code "58") (name "unconnected-(IC2-(A14)PC6-Pad41)") (class "Default")
      (node (ref "IC2") (pin "41") (pinfunction "(A14)PC6_41") (pintype "bidirectional"))
    )
    (net (code "59") (name "unconnected-(IC2-(A15)PC7-Pad42)") (class "Default")
      (node (ref "IC2") (pin "42") (pinfunction "(A15)PC7_42") (pintype "bidirectional"))
    )
    (net (code "60") (name "unconnected-(IC2-(AD0)PA0-Pad51)") (class "Default")
      (node (ref "IC2") (pin "51") (pinfunction "(AD0)PA0_51") (pintype "bidirectional"))
    )
    (net (code "61") (name "unconnected-(IC2-(AD1)PA1-Pad50)") (class "Default")
      (node (ref "IC2") (pin "50") (pinfunction "(AD1)PA1_50") (pintype "bidirectional"))
    )
    (net (code "62") (name "unconnected-(IC2-(AD2)PA2-Pad49)") (class "Default")
      (node (ref "IC2") (pin "49") (pinfunction "(AD2)PA2_49") (pintype "bidirectional"))
    )
    (net (code "63") (name "unconnected-(IC2-(AD3)PA3-Pad48)") (class "Default")
      (node (ref "IC2") (pin "48") (pinfunction "(AD3)PA3_48") (pintype "bidirectional"))
    )
    (net (code "64") (name "unconnected-(IC2-(AD4)PA4-Pad47)") (class "Default")
      (node (ref "IC2") (pin "47") (pinfunction "(AD4)PA4_47") (pintype "bidirectional"))
    )
    (net (code "65") (name "unconnected-(IC2-(AD5)PA5-Pad46)") (class "Default")
      (node (ref "IC2") (pin "46") (pinfunction "(AD5)PA5_46") (pintype "bidirectional"))
    )
    (net (code "66") (name "unconnected-(IC2-(AD6)PA6-Pad45)") (class "Default")
      (node (ref "IC2") (pin "45") (pinfunction "(AD6)PA6_45") (pintype "bidirectional"))
    )
    (net (code "67") (name "unconnected-(IC2-(AD7)PA7-Pad44)") (class "Default")
      (node (ref "IC2") (pin "44") (pinfunction "(AD7)PA7_44") (pintype "bidirectional"))
    )
    (net (code "68") (name "unconnected-(IC2-(ADC0)PF0-Pad61)") (class "Default")
      (node (ref "IC2") (pin "61") (pinfunction "(ADC0)PF0_61") (pintype "bidirectional"))
    )
    (net (code "69") (name "unconnected-(IC2-(ADC7{slash}TDI)PF7-Pad54)") (class "Default")
      (node (ref "IC2") (pin "54") (pinfunction "(ADC7/TDI)PF7_54") (pintype "bidirectional"))
    )
    (net (code "70") (name "unconnected-(IC2-(ALE)PG2-Pad43)") (class "Default")
      (node (ref "IC2") (pin "43") (pinfunction "(ALE)PG2_43") (pintype "bidirectional"))
    )
    (net (code "71") (name "unconnected-(IC2-(CLKO{slash}ICP3{slash}INT7)PE7-Pad9)") (class "Default")
      (node (ref "IC2") (pin "9") (pinfunction "(CLKO/ICP3/INT7)PE7_9") (pintype "bidirectional"))
    )
    (net (code "72") (name "unconnected-(IC2-(ICP1)PD4-Pad29)") (class "Default")
      (node (ref "IC2") (pin "29") (pinfunction "(ICP1)PD4_29") (pintype "bidirectional"))
    )
    (net (code "73") (name "unconnected-(IC2-(OC1B{slash}PCINT6)PB6-Pad16)") (class "Default")
      (node (ref "IC2") (pin "16") (pinfunction "(OC1B/PCINT6)PB6_16") (pintype "bidirectional"))
    )
    (net (code "74") (name "unconnected-(IC2-(RD)PG1-Pad34)") (class "Default")
      (node (ref "IC2") (pin "34") (pinfunction "(RD)PG1_34") (pintype "bidirectional"))
    )
    (net (code "75") (name "unconnected-(IC2-(SCL{slash}INT0)PD0-Pad25)") (class "Default")
      (node (ref "IC2") (pin "25") (pinfunction "(SCL/INT0)PD0_25") (pintype "bidirectional"))
    )
    (net (code "76") (name "unconnected-(IC2-(SDA{slash}INT1)PD1-Pad26)") (class "Default")
      (node (ref "IC2") (pin "26") (pinfunction "(SDA/INT1)PD1_26") (pintype "bidirectional"))
    )
    (net (code "77") (name "unconnected-(IC2-(SS{slash}PCINT0)PB0-Pad10)") (class "Default")
      (node (ref "IC2") (pin "10") (pinfunction "(SS/PCINT0)PB0_10") (pintype "bidirectional"))
    )
    (net (code "78") (name "unconnected-(IC2-(T0)PD7-Pad32)") (class "Default")
      (node (ref "IC2") (pin "32") (pinfunction "(T0)PD7_32") (pintype "bidirectional"))
    )
    (net (code "79") (name "unconnected-(IC2-(T1)PD6-Pad31)") (class "Default")
      (node (ref "IC2") (pin "31") (pinfunction "(T1)PD6_31") (pintype "bidirectional"))
    )
    (net (code "80") (name "unconnected-(IC2-(T3{slash}INT6)PE6-Pad8)") (class "Default")
      (node (ref "IC2") (pin "8") (pinfunction "(T3/INT6)PE6_8") (pintype "bidirectional"))
    )
    (net (code "81") (name "unconnected-(IC2-(TOSC1)PG4-Pad19)") (class "Default")
      (node (ref "IC2") (pin "19") (pinfunction "(TOSC1)PG4_19") (pintype "bidirectional"))
    )
    (net (code "82") (name "unconnected-(IC2-(TOSC2)PG3-Pad18)") (class "Default")
      (node (ref "IC2") (pin "18") (pinfunction "(TOSC2)PG3_18") (pintype "bidirectional"))
    )
    (net (code "83") (name "unconnected-(IC2-(WR)PG0-Pad33)") (class "Default")
      (node (ref "IC2") (pin "33") (pinfunction "(WR)PG0_33") (pintype "bidirectional"))
    )
    (net (code "84") (name "unconnected-(IC2-(XCK0{slash}AIN0)PE2-Pad4)") (class "Default")
      (node (ref "IC2") (pin "4") (pinfunction "(XCK0/AIN0)PE2_4") (pintype "bidirectional"))
    )
    (net (code "85") (name "unconnected-(IC2-(XCK1)PD5-Pad30)") (class "Default")
      (node (ref "IC2") (pin "30") (pinfunction "(XCK1)PD5_30") (pintype "bidirectional"))
    )
    (net (code "86") (name "unconnected-(U1-DIRN-Pad12)") (class "Default")
      (node (ref "U1") (pin "12") (pinfunction "DIRN_12") (pintype "open_collector"))
    )
    (net (code "87") (name "unconnected-(U1-EXT1-Pad2)") (class "Default")
      (node (ref "U1") (pin "2") (pinfunction "EXT1_2") (pintype "input"))
    )
    (net (code "88") (name "unconnected-(U1-EXT2-Pad7)") (class "Default")
      (node (ref "U1") (pin "7") (pinfunction "EXT2_7") (pintype "input"))
    )
  )
)
